# Fonte12V.net
KiCad netlist of a schematic drawn in EAGLE
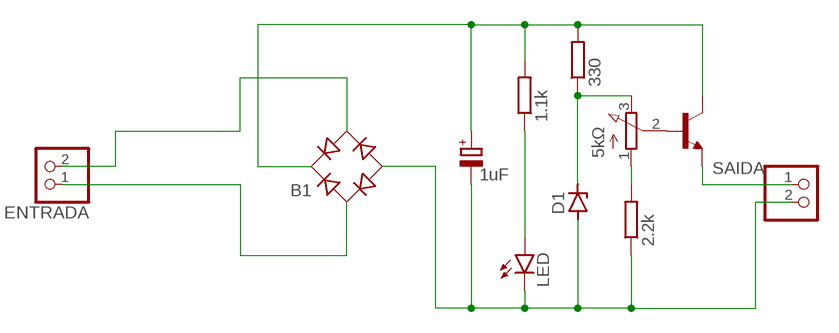
[diagram p0: schematic, sheet 1]

(export (version "E")
  (design (tool "Eeschema 10.0.6"))
  (components
    (comp (ref "B1")
      (value "RB1A")
      (footprint "eagle-import:RB1A")
      (libsource (lib "eagle-import") (part "RB1A"))
    )
    (comp (ref "C1")
      (value "1uF")
      (footprint "eagle-import:E2,5-6E")
      (libsource (lib "eagle-import") (part "CPOL-EUE2,5-6E"))
    )
    (comp (ref "D1")
      (value "ZENER-DIODEDO41Z10")
      (footprint "eagle-import:DO41Z10")
      (libsource (lib "eagle-import") (part "ZENER-DIODEDO41Z10"))
    )
    (comp (ref "ENTRADA")
      (value "PINHD-1X2")
      (footprint "eagle-import:1X02")
      (libsource (lib "eagle-import") (part "PINHD-1X2"))
    )
    (comp (ref "LED")
      (value "TLLR4400")
      (footprint "eagle-import:LED3MM")
      (fields (field (name "MF") "VISHAY SEMICONDUCTOR"))
      (libsource (lib "eagle-import") (part "TLLR4400"))
    )
    (comp (ref "R1")
      (value "1.1k")
      (footprint "eagle-import:0207_10")
      (libsource (lib "eagle-import") (part "R-EU_0207/10"))
    )
    (comp (ref "R2")
      (value "5kΩ")
      (footprint "eagle-import:3RP_1610N")
      (libsource (lib "eagle-import") (part "3RP/1610N"))
    )
    (comp (ref "R3")
      (value "2.2k")
      (footprint "eagle-import:0207_10")
      (libsource (lib "eagle-import") (part "R-EU_0207/10"))
    )
    (comp (ref "R4")
      (value "330")
      (footprint "eagle-import:0207_10")
      (libsource (lib "eagle-import") (part "R-EU_0207/10"))
    )
    (comp (ref "SAIDA")
      (value "PINHD-1X2")
      (footprint "eagle-import:1X02")
      (libsource (lib "eagle-import") (part "PINHD-1X2"))
    )
    (comp (ref "T1")
      (value "2N706")
      (footprint "eagle-import:TO18")
      (libsource (lib "eagle-import") (part "2N706"))
    )
  )
  (nets
    (net (code "1") (name "Net-(B1-PadAC1)") (class "Default")
      (node (ref "B1") (pin "AC1") (pinfunction "AC1_AC1") (pintype "passive"))
      (node (ref "ENTRADA") (pin "1") (pinfunction "1_1") (pintype "passive"))
    )
    (net (code "2") (name "Net-(B1-PadAC2)") (class "Default")
      (node (ref "B1") (pin "AC2") (pinfunction "AC2_AC2") (pintype "passive"))
      (node (ref "ENTRADA") (pin "2") (pinfunction "2_2") (pintype "passive"))
    )
    (net (code "3") (name "Net-(LED-C)") (class "Default")
      (node (ref "B1") (pin "-") (pinfunction "-_-") (pintype "passive"))
      (node (ref "C1") (pin "-") (pinfunction "-_-") (pintype "passive"))
      (node (ref "D1") (pin "A") (pinfunction "A_A") (pintype "passive"))
      (node (ref "LED") (pin "K") (pinfunction "C_K") (pintype "passive"))
      (node (ref "R3") (pin "1") (pinfunction "1_1") (pintype "passive"))
      (node (ref "SAIDA") (pin "2") (pinfunction "2_2") (pintype "passive"))
    )
    (net (code "4") (name "Net-(LED-PadA)") (class "Default")
      (node (ref "LED") (pin "A") (pinfunction "A_A") (pintype "passive"))
      (node (ref "R1") (pin "1") (pinfunction "1_1") (pintype "passive"))
    )
    (net (code "5") (name "Net-(R2-A)") (class "Default")
      (node (ref "R2") (pin "1") (pinfunction "A_1") (pintype "passive"))
      (node (ref "R3") (pin "2") (pinfunction "2_2") (pintype "passive"))
    )
    (net (code "6") (name "Net-(R2-E)") (class "Default")
      (node (ref "D1") (pin "C") (pinfunction "C_C") (pintype "passive"))
      (node (ref "R2") (pin "3") (pinfunction "E_3") (pintype "passive"))
      (node (ref "R4") (pin "1") (pinfunction "1_1") (pintype "passive"))
    )
    (net (code "7") (name "Net-(R2-S)") (class "Default")
      (node (ref "R2") (pin "2") (pinfunction "S_2") (pintype "passive"))
      (node (ref "T1") (pin "2") (pinfunction "B_2") (pintype "passive"))
    )
    (net (code "8") (name "Net-(T1-C)") (class "Default")
      (node (ref "B1") (pin "+") (pinfunction "+_+") (pintype "passive"))
      (node (ref "C1") (pin "+") (pinfunction "+_+") (pintype "passive"))
      (node (ref "R1") (pin "2") (pinfunction "2_2") (pintype "passive"))
      (node (ref "R4") (pin "2") (pinfunction "2_2") (pintype "passive"))
      (node (ref "T1") (pin "3") (pinfunction "C_3") (pintype "passive"))
    )
    (net (code "9") (name "Net-(T1-E)") (class "Default")
      (node (ref "SAIDA") (pin "1") (pinfunction "1_1") (pintype "passive"))
      (node (ref "T1") (pin "1") (pinfunction "E_1") (pintype "passive"))
    )
  )
)
